# pico.net
KiCad netlist of a schematic drawn in EAGLE
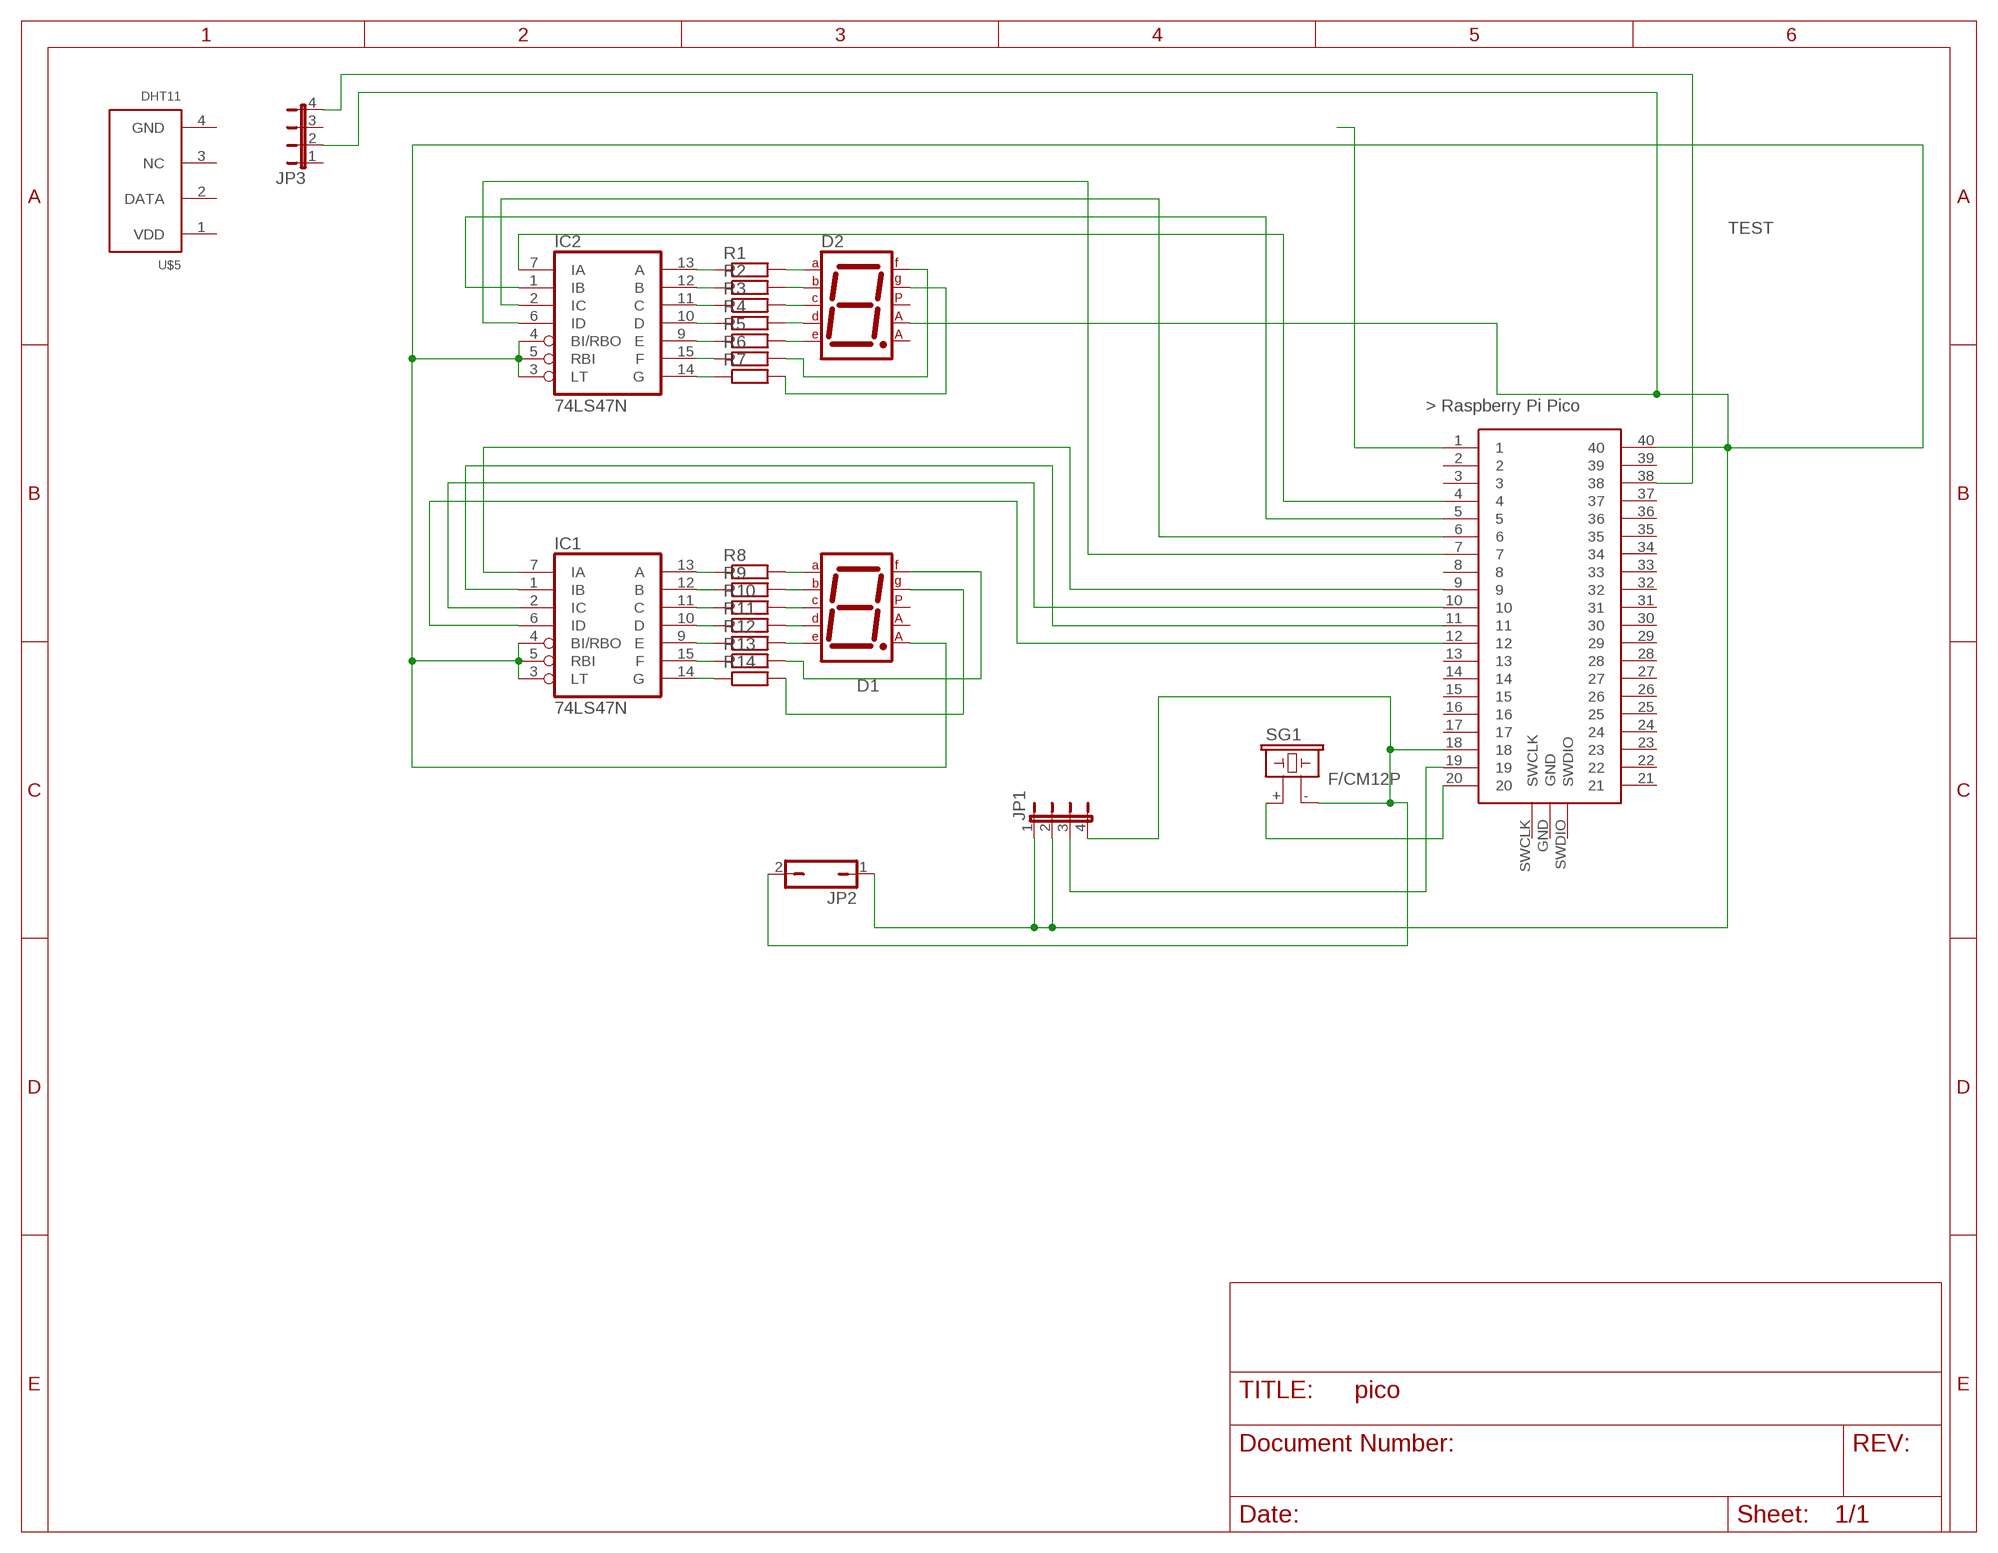
[diagram p0: schematic, sheet 1]

(export (version "E")
  (design (tool "Eeschema 10.0.6"))
  (components
    (comp (ref "D1")
      (value "7SEG-CA")
      (footprint "eagle-import:7SEG-13")
      (libsource (lib "eagle-import") (part "7SEG-CA"))
    )
    (comp (ref "D2")
      (value "7SEG-CA")
      (footprint "eagle-import:7SEG-13")
      (libsource (lib "eagle-import") (part "7SEG-CA"))
    )
    (comp (ref "IC1")
      (value "74LS47N")
      (footprint "eagle-import:DIL16")
      (libsource (lib "eagle-import") (part "7447NLS"))
    )
    (comp (ref "IC2")
      (value "74LS47N")
      (footprint "eagle-import:DIL16")
      (libsource (lib "eagle-import") (part "7447NLS"))
    )
    (comp (ref "JP1")
      (value "JP4E")
      (footprint "eagle-import:JP4")
      (libsource (lib "eagle-import") (part "JP4E"))
    )
    (comp (ref "JP2")
      (value "JP1Q")
      (footprint "eagle-import:JP1")
      (libsource (lib "eagle-import") (part "JP1Q"))
    )
    (comp (ref "JP3")
      (value "JP4E")
      (footprint "eagle-import:JP4")
      (libsource (lib "eagle-import") (part "JP4E"))
    )
    (comp (ref "R1")
      (value "R-EU_0207/12")
      (footprint "eagle-import:0207_12")
      (libsource (lib "eagle-import") (part "R-EU_0207/12"))
    )
    (comp (ref "R2")
      (value "R-EU_0207/12")
      (footprint "eagle-import:0207_12")
      (libsource (lib "eagle-import") (part "R-EU_0207/12"))
    )
    (comp (ref "R3")
      (value "R-EU_0207/12")
      (footprint "eagle-import:0207_12")
      (libsource (lib "eagle-import") (part "R-EU_0207/12"))
    )
    (comp (ref "R4")
      (value "R-EU_0207/12")
      (footprint "eagle-import:0207_12")
      (libsource (lib "eagle-import") (part "R-EU_0207/12"))
    )
    (comp (ref "R5")
      (value "R-EU_0207/12")
      (footprint "eagle-import:0207_12")
      (libsource (lib "eagle-import") (part "R-EU_0207/12"))
    )
    (comp (ref "R6")
      (value "R-EU_0207/12")
      (footprint "eagle-import:0207_12")
      (libsource (lib "eagle-import") (part "R-EU_0207/12"))
    )
    (comp (ref "R7")
      (value "R-EU_0207/12")
      (footprint "eagle-import:0207_12")
      (libsource (lib "eagle-import") (part "R-EU_0207/12"))
    )
    (comp (ref "R8")
      (value "R-EU_0207/12")
      (footprint "eagle-import:0207_12")
      (libsource (lib "eagle-import") (part "R-EU_0207/12"))
    )
    (comp (ref "R9")
      (value "R-EU_0207/12")
      (footprint "eagle-import:0207_12")
      (libsource (lib "eagle-import") (part "R-EU_0207/12"))
    )
    (comp (ref "R10")
      (value "R-EU_0207/12")
      (footprint "eagle-import:0207_12")
      (libsource (lib "eagle-import") (part "R-EU_0207/12"))
    )
    (comp (ref "R11")
      (value "R-EU_0207/12")
      (footprint "eagle-import:0207_12")
      (libsource (lib "eagle-import") (part "R-EU_0207/12"))
    )
    (comp (ref "R12")
      (value "R-EU_0207/12")
      (footprint "eagle-import:0207_12")
      (libsource (lib "eagle-import") (part "R-EU_0207/12"))
    )
    (comp (ref "R13")
      (value "R-EU_0207/12")
      (footprint "eagle-import:0207_12")
      (libsource (lib "eagle-import") (part "R-EU_0207/12"))
    )
    (comp (ref "R14")
      (value "R-EU_0207/12")
      (footprint "eagle-import:0207_12")
      (libsource (lib "eagle-import") (part "R-EU_0207/12"))
    )
    (comp (ref "SG1")
      (value "F/CM12P")
      (footprint "eagle-import:F_CM12P")
      (libsource (lib "eagle-import") (part "F/CM12P"))
    )
    (comp (ref "U$1")
      (value "RASPBERRY-PI-PICO_TH")
      (footprint "eagle-import:FT_RASPBERRY-PI-PICO_TH")
      (libsource (lib "eagle-import") (part "RASPBERRY-PI-PICO_TH"))
    )
    (comp (ref "U$5")
      (value "DHT11")
      (footprint "eagle-import:DHT11")
      (libsource (lib "eagle-import") (part "DHT11"))
    )
  )
  (nets
    (net (code "1") (name "/GND") (class "Default")
      (node (ref "U$5") (pin "4") (pinfunction "GND_4") (pintype "power_in"))
    )
    (net (code "2") (name "/TEST") (class "Default")
      (node (ref "D1") (pin "8") (pinfunction "CA2_8") (pintype "passive"))
      (node (ref "D2") (pin "3") (pinfunction "CA1_3") (pintype "passive"))
      (node (ref "IC1") (pin "3") (pinfunction "LT_3") (pintype "input"))
      (node (ref "IC1") (pin "4") (pinfunction "BI/RBO_4") (pintype "input"))
      (node (ref "IC1") (pin "5") (pinfunction "RBI_5") (pintype "input"))
      (node (ref "IC2") (pin "3") (pinfunction "LT_3") (pintype "input"))
      (node (ref "IC2") (pin "4") (pinfunction "BI/RBO_4") (pintype "input"))
      (node (ref "IC2") (pin "5") (pinfunction "RBI_5") (pintype "input"))
      (node (ref "JP1") (pin "1") (pinfunction "1_1") (pintype "passive"))
      (node (ref "JP1") (pin "2") (pinfunction "2_2") (pintype "passive"))
      (node (ref "JP2") (pin "1") (pinfunction "1_1") (pintype "passive"))
      (node (ref "JP3") (pin "2") (pinfunction "2_2") (pintype "passive"))
      (node (ref "U$1") (pin "40") (pinfunction "40_40") (pintype "bidirectional"))
    )
    (net (code "3") (name "/VDD") (class "Default")
      (node (ref "U$5") (pin "1") (pinfunction "VDD_1") (pintype "power_in"))
    )
    (net (code "4") (name "Net-(D1-A)") (class "Default")
      (node (ref "D1") (pin "7") (pinfunction "A_7") (pintype "passive"))
      (node (ref "R8") (pin "2") (pinfunction "2_2") (pintype "passive"))
    )
    (net (code "5") (name "Net-(D1-B)") (class "Default")
      (node (ref "D1") (pin "6") (pinfunction "B_6") (pintype "passive"))
      (node (ref "R9") (pin "2") (pinfunction "2_2") (pintype "passive"))
    )
    (net (code "6") (name "Net-(D1-C)") (class "Default")
      (node (ref "D1") (pin "4") (pinfunction "C_4") (pintype "passive"))
      (node (ref "R10") (pin "2") (pinfunction "2_2") (pintype "passive"))
    )
    (net (code "7") (name "Net-(D1-D)") (class "Default")
      (node (ref "D1") (pin "2") (pinfunction "D_2") (pintype "passive"))
      (node (ref "R11") (pin "2") (pinfunction "2_2") (pintype "passive"))
    )
    (net (code "8") (name "Net-(D1-E)") (class "Default")
      (node (ref "D1") (pin "1") (pinfunction "E_1") (pintype "passive"))
      (node (ref "R12") (pin "2") (pinfunction "2_2") (pintype "passive"))
    )
    (net (code "9") (name "Net-(D1-F)") (class "Default")
      (node (ref "D1") (pin "9") (pinfunction "F_9") (pintype "passive"))
      (node (ref "R13") (pin "2") (pinfunction "2_2") (pintype "passive"))
    )
    (net (code "10") (name "Net-(D1-G)") (class "Default")
      (node (ref "D1") (pin "10") (pinfunction "G_10") (pintype "passive"))
      (node (ref "R14") (pin "2") (pinfunction "2_2") (pintype "passive"))
    )
    (net (code "11") (name "Net-(D2-A)") (class "Default")
      (node (ref "D2") (pin "7") (pinfunction "A_7") (pintype "passive"))
      (node (ref "R1") (pin "2") (pinfunction "2_2") (pintype "passive"))
    )
    (net (code "12") (name "Net-(D2-B)") (class "Default")
      (node (ref "D2") (pin "6") (pinfunction "B_6") (pintype "passive"))
      (node (ref "R2") (pin "2") (pinfunction "2_2") (pintype "passive"))
    )
    (net (code "13") (name "Net-(D2-C)") (class "Default")
      (node (ref "D2") (pin "4") (pinfunction "C_4") (pintype "passive"))
      (node (ref "R3") (pin "2") (pinfunction "2_2") (pintype "passive"))
    )
    (net (code "14") (name "Net-(D2-D)") (class "Default")
      (node (ref "D2") (pin "2") (pinfunction "D_2") (pintype "passive"))
      (node (ref "R4") (pin "2") (pinfunction "2_2") (pintype "passive"))
    )
    (net (code "15") (name "Net-(D2-E)") (class "Default")
      (node (ref "D2") (pin "1") (pinfunction "E_1") (pintype "passive"))
      (node (ref "R5") (pin "2") (pinfunction "2_2") (pintype "passive"))
    )
    (net (code "16") (name "Net-(D2-F)") (class "Default")
      (node (ref "D2") (pin "9") (pinfunction "F_9") (pintype "passive"))
      (node (ref "R6") (pin "2") (pinfunction "2_2") (pintype "passive"))
    )
    (net (code "17") (name "Net-(D2-G)") (class "Default")
      (node (ref "D2") (pin "10") (pinfunction "G_10") (pintype "passive"))
      (node (ref "R7") (pin "2") (pinfunction "2_2") (pintype "passive"))
    )
    (net (code "18") (name "Net-(IC1A-A)") (class "Default")
      (node (ref "IC1") (pin "13") (pinfunction "A_13") (pintype "output"))
      (node (ref "R8") (pin "1") (pinfunction "1_1") (pintype "passive"))
    )
    (net (code "19") (name "Net-(IC1A-B)") (class "Default")
      (node (ref "IC1") (pin "12") (pinfunction "B_12") (pintype "output"))
      (node (ref "R9") (pin "1") (pinfunction "1_1") (pintype "passive"))
    )
    (net (code "20") (name "Net-(IC1A-C)") (class "Default")
      (node (ref "IC1") (pin "11") (pinfunction "C_11") (pintype "output"))
      (node (ref "R10") (pin "1") (pinfunction "1_1") (pintype "passive"))
    )
    (net (code "21") (name "Net-(IC1A-D)") (class "Default")
      (node (ref "IC1") (pin "10") (pinfunction "D_10") (pintype "output"))
      (node (ref "R11") (pin "1") (pinfunction "1_1") (pintype "passive"))
    )
    (net (code "22") (name "Net-(IC1A-E)") (class "Default")
      (node (ref "IC1") (pin "9") (pinfunction "E_9") (pintype "output"))
      (node (ref "R12") (pin "1") (pinfunction "1_1") (pintype "passive"))
    )
    (net (code "23") (name "Net-(IC1A-F)") (class "Default")
      (node (ref "IC1") (pin "15") (pinfunction "F_15") (pintype "output"))
      (node (ref "R13") (pin "1") (pinfunction "1_1") (pintype "passive"))
    )
    (net (code "24") (name "Net-(IC1A-G)") (class "Default")
      (node (ref "IC1") (pin "14") (pinfunction "G_14") (pintype "output"))
      (node (ref "R14") (pin "1") (pinfunction "1_1") (pintype "passive"))
    )
    (net (code "25") (name "Net-(IC1A-IA)") (class "Default")
      (node (ref "IC1") (pin "7") (pinfunction "IA_7") (pintype "input"))
      (node (ref "U$1") (pin "9") (pinfunction "9_9") (pintype "bidirectional"))
    )
    (net (code "26") (name "Net-(IC1A-IB)") (class "Default")
      (node (ref "IC1") (pin "1") (pinfunction "IB_1") (pintype "input"))
      (node (ref "U$1") (pin "11") (pinfunction "11_11") (pintype "bidirectional"))
    )
    (net (code "27") (name "Net-(IC1A-IC)") (class "Default")
      (node (ref "IC1") (pin "2") (pinfunction "IC_2") (pintype "input"))
      (node (ref "U$1") (pin "10") (pinfunction "10_10") (pintype "bidirectional"))
    )
    (net (code "28") (name "Net-(IC1A-ID)") (class "Default")
      (node (ref "IC1") (pin "6") (pinfunction "ID_6") (pintype "input"))
      (node (ref "U$1") (pin "12") (pinfunction "12_12") (pintype "bidirectional"))
    )
    (net (code "29") (name "Net-(IC2A-A)") (class "Default")
      (node (ref "IC2") (pin "13") (pinfunction "A_13") (pintype "output"))
      (node (ref "R1") (pin "1") (pinfunction "1_1") (pintype "passive"))
    )
    (net (code "30") (name "Net-(IC2A-B)") (class "Default")
      (node (ref "IC2") (pin "12") (pinfunction "B_12") (pintype "output"))
      (node (ref "R2") (pin "1") (pinfunction "1_1") (pintype "passive"))
    )
    (net (code "31") (name "Net-(IC2A-C)") (class "Default")
      (node (ref "IC2") (pin "11") (pinfunction "C_11") (pintype "output"))
      (node (ref "R3") (pin "1") (pinfunction "1_1") (pintype "passive"))
    )
    (net (code "32") (name "Net-(IC2A-D)") (class "Default")
      (node (ref "IC2") (pin "10") (pinfunction "D_10") (pintype "output"))
      (node (ref "R4") (pin "1") (pinfunction "1_1") (pintype "passive"))
    )
    (net (code "33") (name "Net-(IC2A-E)") (class "Default")
      (node (ref "IC2") (pin "9") (pinfunction "E_9") (pintype "output"))
      (node (ref "R5") (pin "1") (pinfunction "1_1") (pintype "passive"))
    )
    (net (code "34") (name "Net-(IC2A-F)") (class "Default")
      (node (ref "IC2") (pin "15") (pinfunction "F_15") (pintype "output"))
      (node (ref "R6") (pin "1") (pinfunction "1_1") (pintype "passive"))
    )
    (net (code "35") (name "Net-(IC2A-G)") (class "Default")
      (node (ref "IC2") (pin "14") (pinfunction "G_14") (pintype "output"))
      (node (ref "R7") (pin "1") (pinfunction "1_1") (pintype "passive"))
    )
    (net (code "36") (name "Net-(IC2A-IA)") (class "Default")
      (node (ref "IC2") (pin "7") (pinfunction "IA_7") (pintype "input"))
      (node (ref "U$1") (pin "4") (pinfunction "4_4") (pintype "bidirectional"))
    )
    (net (code "37") (name "Net-(IC2A-IB)") (class "Default")
      (node (ref "IC2") (pin "1") (pinfunction "IB_1") (pintype "input"))
      (node (ref "U$1") (pin "5") (pinfunction "5_5") (pintype "bidirectional"))
    )
    (net (code "38") (name "Net-(IC2A-IC)") (class "Default")
      (node (ref "IC2") (pin "2") (pinfunction "IC_2") (pintype "input"))
      (node (ref "U$1") (pin "6") (pinfunction "6_6") (pintype "bidirectional"))
    )
    (net (code "39") (name "Net-(IC2A-ID)") (class "Default")
      (node (ref "IC2") (pin "6") (pinfunction "ID_6") (pintype "input"))
      (node (ref "U$1") (pin "7") (pinfunction "7_7") (pintype "bidirectional"))
    )
    (net (code "40") (name "Net-(JP1-Pad3)") (class "Default")
      (node (ref "JP1") (pin "3") (pinfunction "3_3") (pintype "passive"))
      (node (ref "U$1") (pin "19") (pinfunction "19_19") (pintype "bidirectional"))
    )
    (net (code "41") (name "Net-(JP3-Pad4)") (class "Default")
      (node (ref "JP3") (pin "4") (pinfunction "4_4") (pintype "passive"))
      (node (ref "U$1") (pin "38") (pinfunction "38_38") (pintype "bidirectional"))
    )
    (net (code "42") (name "Net-(SG1-1)") (class "Default")
      (node (ref "SG1") (pin "+") (pinfunction "1_+") (pintype "passive"))
      (node (ref "U$1") (pin "20") (pinfunction "20_20") (pintype "bidirectional"))
    )
    (net (code "43") (name "Net-(SG1-2)") (class "Default")
      (node (ref "JP1") (pin "4") (pinfunction "4_4") (pintype "passive"))
      (node (ref "JP2") (pin "2") (pinfunction "2_2") (pintype "passive"))
      (node (ref "SG1") (pin "-") (pinfunction "2_-") (pintype "passive"))
      (node (ref "U$1") (pin "18") (pinfunction "18_18") (pintype "bidirectional"))
    )
    (net (code "44") (name "unconnected-(D1-CA1-Pad3)") (class "Default")
      (node (ref "D1") (pin "3") (pinfunction "CA1_3") (pintype "passive"))
    )
    (net (code "45") (name "unconnected-(D1-DP-Pad5)") (class "Default")
      (node (ref "D1") (pin "5") (pinfunction "DP_5") (pintype "passive"))
    )
    (net (code "46") (name "unconnected-(D2-CA2-Pad8)") (class "Default")
      (node (ref "D2") (pin "8") (pinfunction "CA2_8") (pintype "passive"))
    )
    (net (code "47") (name "unconnected-(D2-DP-Pad5)") (class "Default")
      (node (ref "D2") (pin "5") (pinfunction "DP_5") (pintype "passive"))
    )
    (net (code "48") (name "unconnected-(JP3-Pad1)") (class "Default")
      (node (ref "JP3") (pin "1") (pinfunction "1_1") (pintype "passive"))
    )
    (net (code "49") (name "unconnected-(JP3-Pad3)") (class "Default")
      (node (ref "JP3") (pin "3") (pinfunction "3_3") (pintype "passive"))
    )
    (net (code "50") (name "unconnected-(U$1-Pad1)") (class "Default")
      (node (ref "U$1") (pin "1") (pinfunction "1_1") (pintype "bidirectional"))
    )
    (net (code "51") (name "unconnected-(U$1-Pad2)") (class "Default")
      (node (ref "U$1") (pin "2") (pinfunction "2_2") (pintype "bidirectional"))
    )
    (net (code "52") (name "unconnected-(U$1-Pad3)") (class "Default")
      (node (ref "U$1") (pin "3") (pinfunction "3_3") (pintype "bidirectional"))
    )
    (net (code "53") (name "unconnected-(U$1-Pad8)") (class "Default")
      (node (ref "U$1") (pin "8") (pinfunction "8_8") (pintype "bidirectional"))
    )
    (net (code "54") (name "unconnected-(U$1-Pad13)") (class "Default")
      (node (ref "U$1") (pin "13") (pinfunction "13_13") (pintype "bidirectional"))
    )
    (net (code "55") (name "unconnected-(U$1-Pad14)") (class "Default")
      (node (ref "U$1") (pin "14") (pinfunction "14_14") (pintype "bidirectional"))
    )
    (net (code "56") (name "unconnected-(U$1-Pad15)") (class "Default")
      (node (ref "U$1") (pin "15") (pinfunction "15_15") (pintype "bidirectional"))
    )
    (net (code "57") (name "unconnected-(U$1-Pad16)") (class "Default")
      (node (ref "U$1") (pin "16") (pinfunction "16_16") (pintype "bidirectional"))
    )
    (net (code "58") (name "unconnected-(U$1-Pad17)") (class "Default")
      (node (ref "U$1") (pin "17") (pinfunction "17_17") (pintype "bidirectional"))
    )
    (net (code "59") (name "unconnected-(U$1-Pad21)") (class "Default")
      (node (ref "U$1") (pin "21") (pinfunction "21_21") (pintype "bidirectional"))
    )
    (net (code "60") (name "unconnected-(U$1-Pad22)") (class "Default")
      (node (ref "U$1") (pin "22") (pinfunction "22_22") (pintype "bidirectional"))
    )
    (net (code "61") (name "unconnected-(U$1-Pad23)") (class "Default")
      (node (ref "U$1") (pin "23") (pinfunction "23_23") (pintype "bidirectional"))
    )
    (net (code "62") (name "unconnected-(U$1-Pad24)") (class "Default")
      (node (ref "U$1") (pin "24") (pinfunction "24_24") (pintype "bidirectional"))
    )
    (net (code "63") (name "unconnected-(U$1-Pad25)") (class "Default")
      (node (ref "U$1") (pin "25") (pinfunction "25_25") (pintype "bidirectional"))
    )
    (net (code "64") (name "unconnected-(U$1-Pad26)") (class "Default")
      (node (ref "U$1") (pin "26") (pinfunction "26_26") (pintype "bidirectional"))
    )
    (net (code "65") (name "unconnected-(U$1-Pad27)") (class "Default")
      (node (ref "U$1") (pin "27") (pinfunction "27_27") (pintype "bidirectional"))
    )
    (net (code "66") (name "unconnected-(U$1-Pad28)") (class "Default")
      (node (ref "U$1") (pin "28") (pinfunction "28_28") (pintype "bidirectional"))
    )
    (net (code "67") (name "unconnected-(U$1-Pad29)") (class "Default")
      (node (ref "U$1") (pin "29") (pinfunction "29_29") (pintype "bidirectional"))
    )
    (net (code "68") (name "unconnected-(U$1-Pad30)") (class "Default")
      (node (ref "U$1") (pin "30") (pinfunction "30_30") (pintype "bidirectional"))
    )
    (net (code "69") (name "unconnected-(U$1-Pad31)") (class "Default")
      (node (ref "U$1") (pin "31") (pinfunction "31_31") (pintype "bidirectional"))
    )
    (net (code "70") (name "unconnected-(U$1-Pad32)") (class "Default")
      (node (ref "U$1") (pin "32") (pinfunction "32_32") (pintype "bidirectional"))
    )
    (net (code "71") (name "unconnected-(U$1-Pad33)") (class "Default")
      (node (ref "U$1") (pin "33") (pinfunction "33_33") (pintype "bidirectional"))
    )
    (net (code "72") (name "unconnected-(U$1-Pad34)") (class "Default")
      (node (ref "U$1") (pin "34") (pinfunction "34_34") (pintype "bidirectional"))
    )
    (net (code "73") (name "unconnected-(U$1-Pad35)") (class "Default")
      (node (ref "U$1") (pin "35") (pinfunction "35_35") (pintype "bidirectional"))
    )
    (net (code "74") (name "unconnected-(U$1-Pad36)") (class "Default")
      (node (ref "U$1") (pin "36") (pinfunction "36_36") (pintype "bidirectional"))
    )
    (net (code "75") (name "unconnected-(U$1-Pad37)") (class "Default")
      (node (ref "U$1") (pin "37") (pinfunction "37_37") (pintype "bidirectional"))
    )
    (net (code "76") (name "unconnected-(U$1-Pad39)") (class "Default")
      (node (ref "U$1") (pin "39") (pinfunction "39_39") (pintype "bidirectional"))
    )
    (net (code "77") (name "unconnected-(U$1-PadGND)") (class "Default")
      (node (ref "U$1") (pin "GND") (pinfunction "GND_GND") (pintype "bidirectional"))
    )
    (net (code "78") (name "unconnected-(U$1-PadSWCLK)") (class "Default")
      (node (ref "U$1") (pin "SWCLK") (pinfunction "SWCLK_SWCLK") (pintype "bidirectional"))
    )
    (net (code "79") (name "unconnected-(U$1-PadSWDIO)") (class "Default")
      (node (ref "U$1") (pin "SWDIO") (pinfunction "SWDIO_SWDIO") (pintype "bidirectional"))
    )
    (net (code "80") (name "unconnected-(U$5-DATA-Pad2)") (class "Default")
      (node (ref "U$5") (pin "2") (pinfunction "DATA_2") (pintype "bidirectional"))
    )
    (net (code "81") (name "unconnected-(U$5-NC-Pad3)") (class "Default")
      (node (ref "U$5") (pin "3") (pinfunction "NC_3") (pintype "bidirectional"))
    )
  )
)
